# adapter-STDC14-DIL.net
KiCad netlist of a schematic drawn in EAGLE
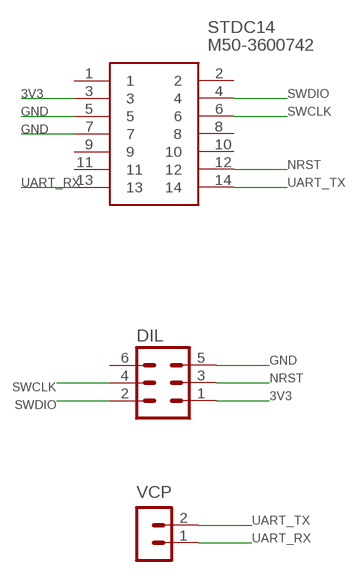
[diagram p0: schematic, sheet 1]

(export (version "E")
  (design (tool "Eeschema 10.0.6"))
  (components
    (comp (ref "DIL")
      (value "MA03-2")
      (footprint "eagle-import:MA03-2")
      (libsource (lib "eagle-import") (part "MA03-2"))
    )
    (comp (ref "STDC14")
      (value "M50-3600742")
      (footprint "eagle-import:M50-3600742")
      (fields (field (name "MOUSER_PART_NUMBER") "855-M50-3600742"))
      (libsource (lib "eagle-import") (part "M50-3600742"))
    )
    (comp (ref "VCP")
      (value "MA02-1")
      (footprint "eagle-import:MA02-1")
      (libsource (lib "eagle-import") (part "MA02-1"))
    )
  )
  (nets
    (net (code "1") (name "/3V3") (class "Default")
      (node (ref "DIL") (pin "1") (pinfunction "1_1") (pintype "passive"))
      (node (ref "STDC14") (pin "3") (pinfunction "3_3") (pintype "bidirectional"))
    )
    (net (code "2") (name "/GND") (class "Default")
      (node (ref "DIL") (pin "5") (pinfunction "5_5") (pintype "passive"))
      (node (ref "STDC14") (pin "5") (pinfunction "5_5") (pintype "bidirectional"))
      (node (ref "STDC14") (pin "7") (pinfunction "7_7") (pintype "bidirectional"))
    )
    (net (code "3") (name "/NRST") (class "Default")
      (node (ref "DIL") (pin "3") (pinfunction "3_3") (pintype "passive"))
      (node (ref "STDC14") (pin "12") (pinfunction "12_12") (pintype "bidirectional"))
    )
    (net (code "4") (name "/SWCLK") (class "Default")
      (node (ref "DIL") (pin "4") (pinfunction "4_4") (pintype "passive"))
      (node (ref "STDC14") (pin "6") (pinfunction "6_6") (pintype "bidirectional"))
    )
    (net (code "5") (name "/SWDIO") (class "Default")
      (node (ref "DIL") (pin "2") (pinfunction "2_2") (pintype "passive"))
      (node (ref "STDC14") (pin "4") (pinfunction "4_4") (pintype "bidirectional"))
    )
    (net (code "6") (name "/UART_RX") (class "Default")
      (node (ref "STDC14") (pin "13") (pinfunction "13_13") (pintype "bidirectional"))
      (node (ref "VCP") (pin "1") (pinfunction "1_1") (pintype "passive"))
    )
    (net (code "7") (name "/UART_TX") (class "Default")
      (node (ref "STDC14") (pin "14") (pinfunction "14_14") (pintype "bidirectional"))
      (node (ref "VCP") (pin "2") (pinfunction "2_2") (pintype "passive"))
    )
    (net (code "8") (name "unconnected-(DIL-Pad6)") (class "Default")
      (node (ref "DIL") (pin "6") (pinfunction "6_6") (pintype "passive"))
    )
    (net (code "9") (name "unconnected-(STDC14-Pad1)") (class "Default")
      (node (ref "STDC14") (pin "1") (pinfunction "1_1") (pintype "bidirectional"))
    )
    (net (code "10") (name "unconnected-(STDC14-Pad2)") (class "Default")
      (node (ref "STDC14") (pin "2") (pinfunction "2_2") (pintype "bidirectional"))
    )
    (net (code "11") (name "unconnected-(STDC14-Pad8)") (class "Default")
      (node (ref "STDC14") (pin "8") (pinfunction "8_8") (pintype "bidirectional"))
    )
    (net (code "12") (name "unconnected-(STDC14-Pad9)") (class "Default")
      (node (ref "STDC14") (pin "9") (pinfunction "9_9") (pintype "bidirectional"))
    )
    (net (code "13") (name "unconnected-(STDC14-Pad10)") (class "Default")
      (node (ref "STDC14") (pin "10") (pinfunction "10_10") (pintype "bidirectional"))
    )
    (net (code "14") (name "unconnected-(STDC14-Pad11)") (class "Default")
      (node (ref "STDC14") (pin "11") (pinfunction "11_11") (pintype "bidirectional"))
    )
  )
)
